# V2_0_2_USB_Hub_Switch.net
KiCad netlist of a schematic drawn in EasyEDA Pro
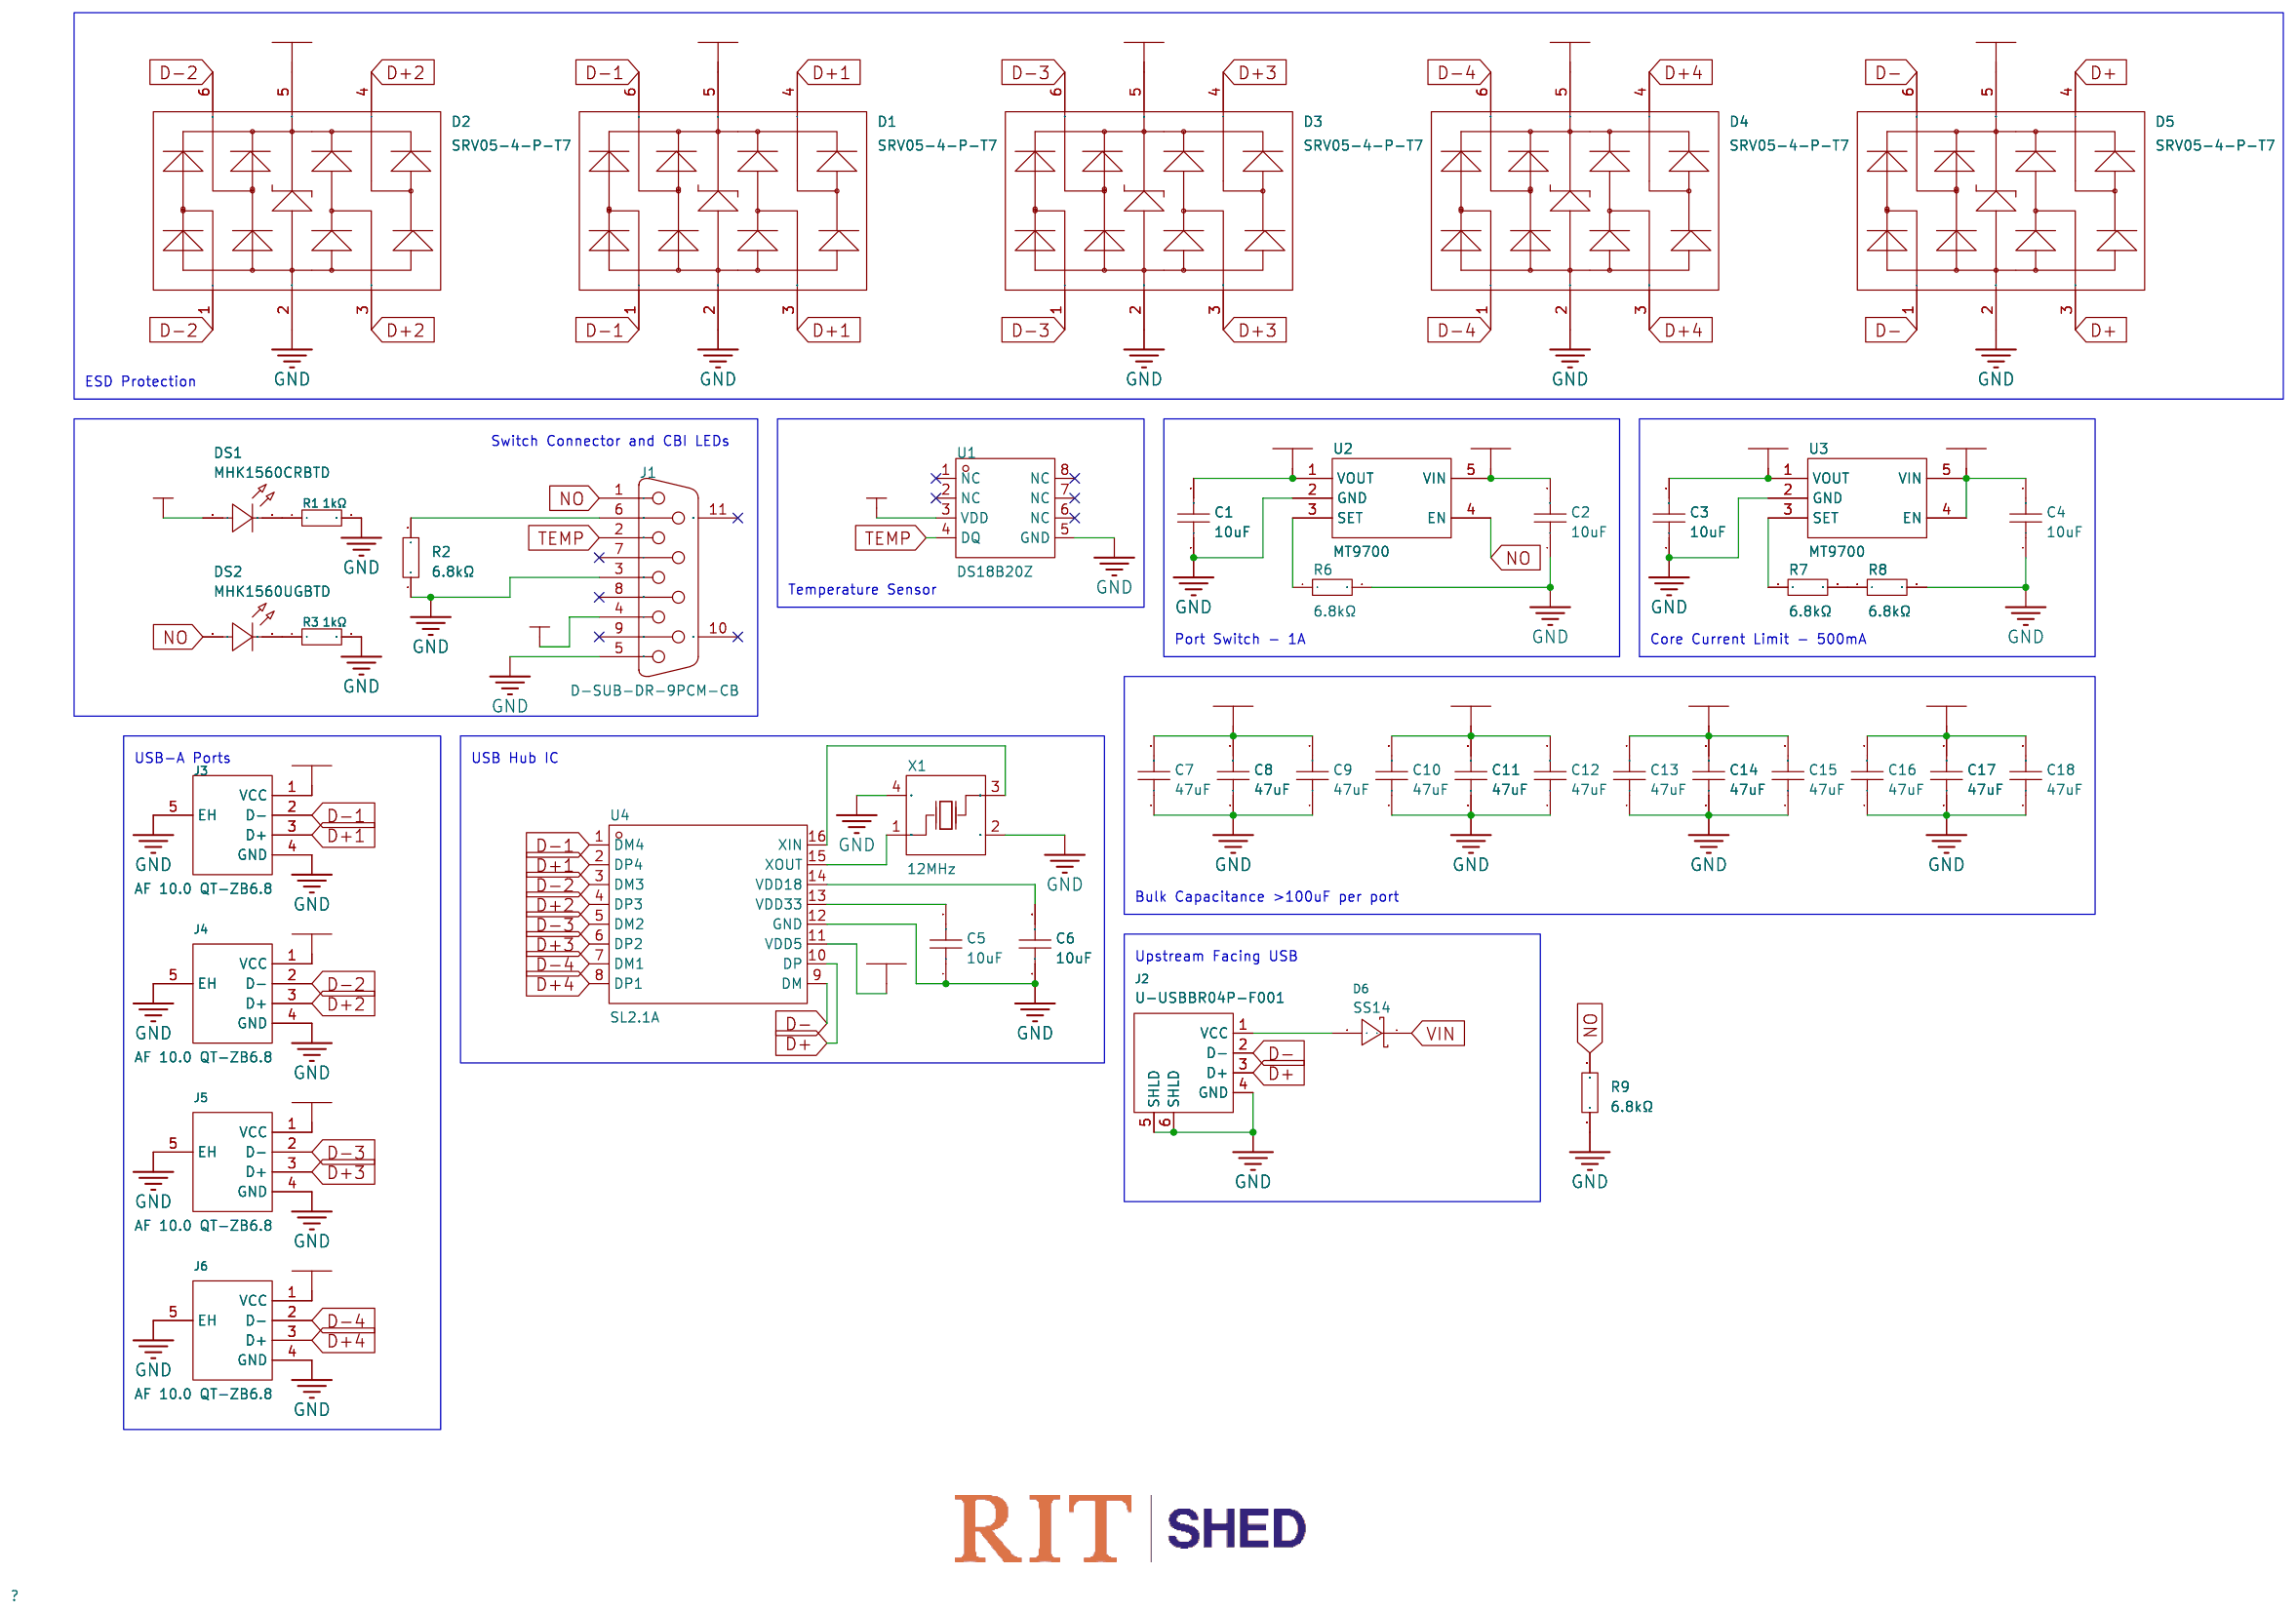
[diagram p0: schematic sheet]

(export (version "E")
  (design (tool "Eeschema 10.0.6"))
  (components
    (comp (ref "C1")
      (value "10uF")
      (footprint "easyedapro:C0603")
      (fields
        (field (name "Manufacturer Part") "CL10A106MA8NRNC")
        (field (name "Manufacturer") "SAMSUNG(三星)")
      )
      (libsource (lib "easyedapro") (part "CL10A106MA8NRNC"))
    )
    (comp (ref "C2")
      (value "10uF")
      (footprint "easyedapro:C0603")
      (fields
        (field (name "Manufacturer Part") "CL10A106MA8NRNC")
        (field (name "Manufacturer") "SAMSUNG(三星)")
      )
      (libsource (lib "easyedapro") (part "CL10A106MA8NRNC"))
    )
    (comp (ref "C3")
      (value "10uF")
      (footprint "easyedapro:C0603")
      (fields
        (field (name "Manufacturer Part") "CL10A106MA8NRNC")
        (field (name "Manufacturer") "SAMSUNG(三星)")
      )
      (libsource (lib "easyedapro") (part "CL10A106MA8NRNC"))
    )
    (comp (ref "C4")
      (value "10uF")
      (footprint "easyedapro:C0603")
      (fields
        (field (name "Manufacturer Part") "CL10A106MA8NRNC")
        (field (name "Manufacturer") "SAMSUNG(三星)")
      )
      (libsource (lib "easyedapro") (part "CL10A106MA8NRNC"))
    )
    (comp (ref "C5")
      (value "10uF")
      (footprint "easyedapro:C0603")
      (fields
        (field (name "Manufacturer Part") "CL10A106MA8NRNC")
        (field (name "Manufacturer") "SAMSUNG(三星)")
      )
      (libsource (lib "easyedapro") (part "CL10A106MA8NRNC"))
    )
    (comp (ref "C6")
      (value "10uF")
      (footprint "easyedapro:C0603")
      (fields
        (field (name "Manufacturer Part") "CL10A106MA8NRNC")
        (field (name "Manufacturer") "SAMSUNG(三星)")
      )
      (libsource (lib "easyedapro") (part "CL10A106MA8NRNC"))
    )
    (comp (ref "C7")
      (value "47uF")
      (footprint "easyedapro:C1206")
      (fields
        (field (name "Manufacturer Part") "CL31A476MPHNNNE")
        (field (name "Manufacturer") "SAMSUNG(三星)")
      )
      (libsource (lib "easyedapro") (part "CL31A476MPHNNNE"))
    )
    (comp (ref "C8")
      (value "47uF")
      (footprint "easyedapro:C1206")
      (fields
        (field (name "Manufacturer Part") "CL31A476MPHNNNE")
        (field (name "Manufacturer") "SAMSUNG(三星)")
      )
      (libsource (lib "easyedapro") (part "CL31A476MPHNNNE"))
    )
    (comp (ref "C9")
      (value "47uF")
      (footprint "easyedapro:C1206")
      (fields
        (field (name "Manufacturer Part") "CL31A476MPHNNNE")
        (field (name "Manufacturer") "SAMSUNG(三星)")
      )
      (libsource (lib "easyedapro") (part "CL31A476MPHNNNE"))
    )
    (comp (ref "C10")
      (value "47uF")
      (footprint "easyedapro:C1206")
      (fields
        (field (name "Manufacturer Part") "CL31A476MPHNNNE")
        (field (name "Manufacturer") "SAMSUNG(三星)")
      )
      (libsource (lib "easyedapro") (part "CL31A476MPHNNNE"))
    )
    (comp (ref "C11")
      (value "47uF")
      (footprint "easyedapro:C1206")
      (fields
        (field (name "Manufacturer Part") "CL31A476MPHNNNE")
        (field (name "Manufacturer") "SAMSUNG(三星)")
      )
      (libsource (lib "easyedapro") (part "CL31A476MPHNNNE"))
    )
    (comp (ref "C12")
      (value "47uF")
      (footprint "easyedapro:C1206")
      (fields
        (field (name "Manufacturer Part") "CL31A476MPHNNNE")
        (field (name "Manufacturer") "SAMSUNG(三星)")
      )
      (libsource (lib "easyedapro") (part "CL31A476MPHNNNE"))
    )
    (comp (ref "C13")
      (value "47uF")
      (footprint "easyedapro:C1206")
      (fields
        (field (name "Manufacturer Part") "CL31A476MPHNNNE")
        (field (name "Manufacturer") "SAMSUNG(三星)")
      )
      (libsource (lib "easyedapro") (part "CL31A476MPHNNNE"))
    )
    (comp (ref "C14")
      (value "47uF")
      (footprint "easyedapro:C1206")
      (fields
        (field (name "Manufacturer Part") "CL31A476MPHNNNE")
        (field (name "Manufacturer") "SAMSUNG(三星)")
      )
      (libsource (lib "easyedapro") (part "CL31A476MPHNNNE"))
    )
    (comp (ref "C15")
      (value "47uF")
      (footprint "easyedapro:C1206")
      (fields
        (field (name "Manufacturer Part") "CL31A476MPHNNNE")
        (field (name "Manufacturer") "SAMSUNG(三星)")
      )
      (libsource (lib "easyedapro") (part "CL31A476MPHNNNE"))
    )
    (comp (ref "C16")
      (value "47uF")
      (footprint "easyedapro:C1206")
      (fields
        (field (name "Manufacturer Part") "CL31A476MPHNNNE")
        (field (name "Manufacturer") "SAMSUNG(三星)")
      )
      (libsource (lib "easyedapro") (part "CL31A476MPHNNNE"))
    )
    (comp (ref "C17")
      (value "47uF")
      (footprint "easyedapro:C1206")
      (fields
        (field (name "Manufacturer Part") "CL31A476MPHNNNE")
        (field (name "Manufacturer") "SAMSUNG(三星)")
      )
      (libsource (lib "easyedapro") (part "CL31A476MPHNNNE"))
    )
    (comp (ref "C18")
      (value "47uF")
      (footprint "easyedapro:C1206")
      (fields
        (field (name "Manufacturer Part") "CL31A476MPHNNNE")
        (field (name "Manufacturer") "SAMSUNG(三星)")
      )
      (libsource (lib "easyedapro") (part "CL31A476MPHNNNE"))
    )
    (comp (ref "D1")
      (value "SRV05-4-P-T7")
      (footprint "easyedapro:SOT-23-6_L2.9-W1.6-P0.95-LS2.8-BR")
      (fields (field (name "Manufacturer") "PROTEK"))
      (libsource (lib "easyedapro") (part "SRV05-4-P-T7"))
    )
    (comp (ref "D2")
      (value "SRV05-4-P-T7")
      (footprint "easyedapro:SOT-23-6_L2.9-W1.6-P0.95-LS2.8-BR")
      (fields (field (name "Manufacturer") "PROTEK"))
      (libsource (lib "easyedapro") (part "SRV05-4-P-T7"))
    )
    (comp (ref "D3")
      (value "SRV05-4-P-T7")
      (footprint "easyedapro:SOT-23-6_L2.9-W1.6-P0.95-LS2.8-BR")
      (fields (field (name "Manufacturer") "PROTEK"))
      (libsource (lib "easyedapro") (part "SRV05-4-P-T7"))
    )
    (comp (ref "D4")
      (value "SRV05-4-P-T7")
      (footprint "easyedapro:SOT-23-6_L2.9-W1.6-P0.95-LS2.8-BR")
      (fields (field (name "Manufacturer") "PROTEK"))
      (libsource (lib "easyedapro") (part "SRV05-4-P-T7"))
    )
    (comp (ref "D5")
      (value "SRV05-4-P-T7")
      (footprint "easyedapro:SOT-23-6_L2.9-W1.6-P0.95-LS2.8-BR")
      (fields (field (name "Manufacturer") "PROTEK"))
      (libsource (lib "easyedapro") (part "SRV05-4-P-T7"))
    )
    (comp (ref "D6")
      (value "SS14")
      (footprint "easyedapro:SMA_L4.2-W2.6-LS5.3-RD")
      (fields (field (name "Manufacturer") "MDD"))
      (libsource (lib "easyedapro") (part "SS14"))
    )
    (comp (ref "DS1")
      (value "MHK1560CRBTD")
      (footprint "easyedapro:LED-TH_MHK1560UGBTD")
      (fields (field (name "Manufacturer") "MEIHUA(美华)"))
      (libsource (lib "easyedapro") (part "MHK1560CGBTD"))
    )
    (comp (ref "DS2")
      (value "MHK1560UGBTD")
      (footprint "easyedapro:LED-TH_MHK1560UGBTD")
      (fields (field (name "Manufacturer") "MEIHUA(美华)"))
      (libsource (lib "easyedapro") (part "MHK1560UGBTD"))
    )
    (comp (ref "J1")
      (value "D-SUB-DR-9PCM-CB")
      (footprint "easyedapro:DB9-TH_ID09S33E4GV00LF")
      (fields (field (name "Manufacturer") "XUNPU(讯普)"))
      (libsource (lib "easyedapro") (part "D-SUB-DR-9PCM-CB"))
    )
    (comp (ref "J2")
      (value "U-USBBR04P-F001")
      (footprint "easyedapro:USB-B-TH_U241-041N-1BR85-1")
      (fields (field (name "Manufacturer") "Ckmtw(灿科盟)"))
      (libsource (lib "easyedapro") (part "U-USBBR04P-F001"))
    )
    (comp (ref "J3")
      (value "AF 10.0 QT-ZB6.8")
      (footprint "easyedapro:USB-A-SMD_AF-10.0-QT-ZB6.8")
      (fields (field (name "Manufacturer") "SHOU HAN(首韩)"))
      (libsource (lib "easyedapro") (part "AF 10.0 QT-ZB6.8"))
    )
    (comp (ref "J4")
      (value "AF 10.0 QT-ZB6.8")
      (footprint "easyedapro:USB-A-SMD_AF-10.0-QT-ZB6.8")
      (fields (field (name "Manufacturer") "SHOU HAN(首韩)"))
      (libsource (lib "easyedapro") (part "AF 10.0 QT-ZB6.8"))
    )
    (comp (ref "J5")
      (value "AF 10.0 QT-ZB6.8")
      (footprint "easyedapro:USB-A-SMD_AF-10.0-QT-ZB6.8")
      (fields (field (name "Manufacturer") "SHOU HAN(首韩)"))
      (libsource (lib "easyedapro") (part "AF 10.0 QT-ZB6.8"))
    )
    (comp (ref "J6")
      (value "AF 10.0 QT-ZB6.8")
      (footprint "easyedapro:USB-A-SMD_AF-10.0-QT-ZB6.8")
      (fields (field (name "Manufacturer") "SHOU HAN(首韩)"))
      (libsource (lib "easyedapro") (part "AF 10.0 QT-ZB6.8"))
    )
    (comp (ref "R1")
      (value "1kΩ")
      (footprint "easyedapro:R0603")
      (fields
        (field (name "Manufacturer Part") "0603WAF1001T5E")
        (field (name "Manufacturer") "UNI-ROYAL(厚声)")
      )
      (libsource (lib "easyedapro") (part "0603WAF1001T5E"))
    )
    (comp (ref "R2")
      (value "6.8kΩ")
      (footprint "easyedapro:R0603")
      (fields
        (field (name "Manufacturer Part") "0603WAF6801T5E")
        (field (name "Manufacturer") "UNI-ROYAL(厚声)")
      )
      (libsource (lib "easyedapro") (part "0603WAF6801T5E"))
    )
    (comp (ref "R3")
      (value "1kΩ")
      (footprint "easyedapro:R0603")
      (fields
        (field (name "Manufacturer Part") "0603WAF1001T5E")
        (field (name "Manufacturer") "UNI-ROYAL(厚声)")
      )
      (libsource (lib "easyedapro") (part "0603WAF1001T5E"))
    )
    (comp (ref "R6")
      (value "6.8kΩ")
      (footprint "easyedapro:R0603")
      (fields
        (field (name "Manufacturer Part") "0603WAF6801T5E")
        (field (name "Manufacturer") "UNI-ROYAL(厚声)")
      )
      (libsource (lib "easyedapro") (part "0603WAF6801T5E"))
    )
    (comp (ref "R7")
      (value "6.8kΩ")
      (footprint "easyedapro:R0603")
      (fields
        (field (name "Manufacturer Part") "0603WAF6801T5E")
        (field (name "Manufacturer") "UNI-ROYAL(厚声)")
      )
      (libsource (lib "easyedapro") (part "0603WAF6801T5E"))
    )
    (comp (ref "R8")
      (value "6.8kΩ")
      (footprint "easyedapro:R0603")
      (fields
        (field (name "Manufacturer Part") "0603WAF6801T5E")
        (field (name "Manufacturer") "UNI-ROYAL(厚声)")
      )
      (libsource (lib "easyedapro") (part "0603WAF6801T5E"))
    )
    (comp (ref "R9")
      (value "6.8kΩ")
      (footprint "easyedapro:R0603")
      (fields
        (field (name "Manufacturer Part") "0603WAF6801T5E")
        (field (name "Manufacturer") "UNI-ROYAL(厚声)")
      )
      (libsource (lib "easyedapro") (part "0603WAF6801T5E"))
    )
    (comp (ref "U1")
      (value "DS18B20Z")
      (footprint "easyedapro:SOP-8_L4.9-W3.9-P1.27-LS6.0-BL")
      (description "Resolution:±0.4°C Resolution:±0.4°C Supply Voltage:2.5V~5.5V Supply Voltage:2.5V~5.5V")
      (fields (field (name "Manufacturer") "UMW(友台半导体)"))
      (libsource (lib "easyedapro") (part "DS18B20Z"))
    )
    (comp (ref "U2")
      (value "MT9700")
      (footprint "easyedapro:SOT-23-5_L3.0-W1.7-P0.95-LS2.8-BR")
      (fields (field (name "Manufacturer") "西安航天民芯"))
      (libsource (lib "easyedapro") (part "MT9700"))
    )
    (comp (ref "U3")
      (value "MT9700")
      (footprint "easyedapro:SOT-23-5_L3.0-W1.7-P0.95-LS2.8-BR")
      (fields (field (name "Manufacturer") "西安航天民芯"))
      (libsource (lib "easyedapro") (part "MT9700"))
    )
    (comp (ref "U4")
      (value "SL2.1A")
      (footprint "easyedapro:SOP-16_L10.0-W3.9-P1.27-LS6.0-BL")
      (fields (field (name "Manufacturer") "CoreChips(和芯润德)"))
      (libsource (lib "easyedapro") (part "SL2.1A"))
    )
    (comp (ref "X1")
      (value "12MHz")
      (footprint "easyedapro:OSC-SMD_4P-L3.2-W2.5-BL")
      (fields (field (name "Manufacturer Part") "X322512MSB4SI") (field (name "Manufacturer") "YXC(扬兴晶振)"))
      (libsource (lib "easyedapro") (part "X322512MSB4SI"))
    )
  )
  (nets
    (net (code "1") (name "D+") (class "Default")
      (node (ref "D5") (pin "3") (pinfunction "3_3") (pintype "input"))
      (node (ref "D5") (pin "4") (pinfunction "4_4") (pintype "input"))
      (node (ref "J2") (pin "3") (pinfunction "D+_3") (pintype "input"))
      (node (ref "U4") (pin "10") (pinfunction "DP_10") (pintype "input"))
    )
    (net (code "2") (name "D+1") (class "Default")
      (node (ref "D1") (pin "3") (pinfunction "3_3") (pintype "input"))
      (node (ref "D1") (pin "4") (pinfunction "4_4") (pintype "input"))
      (node (ref "J3") (pin "3") (pinfunction "D+_3") (pintype "input"))
      (node (ref "U4") (pin "2") (pinfunction "DP4_2") (pintype "input"))
    )
    (net (code "3") (name "D+2") (class "Default")
      (node (ref "D2") (pin "3") (pinfunction "3_3") (pintype "input"))
      (node (ref "D2") (pin "4") (pinfunction "4_4") (pintype "input"))
      (node (ref "J4") (pin "3") (pinfunction "D+_3") (pintype "input"))
      (node (ref "U4") (pin "4") (pinfunction "DP3_4") (pintype "input"))
    )
    (net (code "4") (name "D+3") (class "Default")
      (node (ref "D3") (pin "3") (pinfunction "3_3") (pintype "input"))
      (node (ref "D3") (pin "4") (pinfunction "4_4") (pintype "input"))
      (node (ref "J5") (pin "3") (pinfunction "D+_3") (pintype "input"))
      (node (ref "U4") (pin "6") (pinfunction "DP2_6") (pintype "input"))
    )
    (net (code "5") (name "D+4") (class "Default")
      (node (ref "D4") (pin "3") (pinfunction "3_3") (pintype "input"))
      (node (ref "D4") (pin "4") (pinfunction "4_4") (pintype "input"))
      (node (ref "J6") (pin "3") (pinfunction "D+_3") (pintype "input"))
      (node (ref "U4") (pin "8") (pinfunction "DP1_8") (pintype "input"))
    )
    (net (code "6") (name "D-") (class "Default")
      (node (ref "D5") (pin "1") (pinfunction "1_1") (pintype "input"))
      (node (ref "D5") (pin "6") (pinfunction "6_6") (pintype "input"))
      (node (ref "J2") (pin "2") (pinfunction "D-_2") (pintype "input"))
      (node (ref "U4") (pin "9") (pinfunction "DM_9") (pintype "input"))
    )
    (net (code "7") (name "D-1") (class "Default")
      (node (ref "D1") (pin "1") (pinfunction "1_1") (pintype "input"))
      (node (ref "D1") (pin "6") (pinfunction "6_6") (pintype "input"))
      (node (ref "J3") (pin "2") (pinfunction "D-_2") (pintype "input"))
      (node (ref "U4") (pin "1") (pinfunction "DM4_1") (pintype "input"))
    )
    (net (code "8") (name "D-2") (class "Default")
      (node (ref "D2") (pin "1") (pinfunction "1_1") (pintype "input"))
      (node (ref "D2") (pin "6") (pinfunction "6_6") (pintype "input"))
      (node (ref "J4") (pin "2") (pinfunction "D-_2") (pintype "input"))
      (node (ref "U4") (pin "3") (pinfunction "DM3_3") (pintype "input"))
    )
    (net (code "9") (name "D-3") (class "Default")
      (node (ref "D3") (pin "1") (pinfunction "1_1") (pintype "input"))
      (node (ref "D3") (pin "6") (pinfunction "6_6") (pintype "input"))
      (node (ref "J5") (pin "2") (pinfunction "D-_2") (pintype "input"))
      (node (ref "U4") (pin "5") (pinfunction "DM2_5") (pintype "input"))
    )
    (net (code "10") (name "D-4") (class "Default")
      (node (ref "D4") (pin "1") (pinfunction "1_1") (pintype "input"))
      (node (ref "D4") (pin "6") (pinfunction "6_6") (pintype "input"))
      (node (ref "J6") (pin "2") (pinfunction "D-_2") (pintype "input"))
      (node (ref "U4") (pin "7") (pinfunction "DM1_7") (pintype "input"))
    )
    (net (code "11") (name "GND") (class "Default")
      (node (ref "C1") (pin "1") (pinfunction "1_1") (pintype "input"))
      (node (ref "C10") (pin "1") (pinfunction "1_1") (pintype "input"))
      (node (ref "C11") (pin "1") (pinfunction "1_1") (pintype "input"))
      (node (ref "C12") (pin "1") (pinfunction "1_1") (pintype "input"))
      (node (ref "C13") (pin "1") (pinfunction "1_1") (pintype "input"))
      (node (ref "C14") (pin "1") (pinfunction "1_1") (pintype "input"))
      (node (ref "C15") (pin "1") (pinfunction "1_1") (pintype "input"))
      (node (ref "C16") (pin "1") (pinfunction "1_1") (pintype "input"))
      (node (ref "C17") (pin "1") (pinfunction "1_1") (pintype "input"))
      (node (ref "C18") (pin "1") (pinfunction "1_1") (pintype "input"))
      (node (ref "C2") (pin "1") (pinfunction "1_1") (pintype "input"))
      (node (ref "C3") (pin "1") (pinfunction "1_1") (pintype "input"))
      (node (ref "C4") (pin "1") (pinfunction "1_1") (pintype "input"))
      (node (ref "C5") (pin "1") (pinfunction "1_1") (pintype "input"))
      (node (ref "C6") (pin "1") (pinfunction "1_1") (pintype "input"))
      (node (ref "C7") (pin "1") (pinfunction "1_1") (pintype "input"))
      (node (ref "C8") (pin "1") (pinfunction "1_1") (pintype "input"))
      (node (ref "C9") (pin "1") (pinfunction "1_1") (pintype "input"))
      (node (ref "D1") (pin "2") (pinfunction "2_2") (pintype "input"))
      (node (ref "D2") (pin "2") (pinfunction "2_2") (pintype "input"))
      (node (ref "D3") (pin "2") (pinfunction "2_2") (pintype "input"))
      (node (ref "D4") (pin "2") (pinfunction "2_2") (pintype "input"))
      (node (ref "D5") (pin "2") (pinfunction "2_2") (pintype "input"))
      (node (ref "J1") (pin "3") (pinfunction "3_3") (pintype "input"))
      (node (ref "J1") (pin "5") (pinfunction "5_5") (pintype "input"))
      (node (ref "J2") (pin "4") (pinfunction "GND_4") (pintype "input"))
      (node (ref "J2") (pin "5") (pinfunction "SHLD_5") (pintype "input"))
      (node (ref "J2") (pin "6") (pinfunction "SHLD_6") (pintype "input"))
      (node (ref "J3") (pin "4") (pinfunction "GND_4") (pintype "input"))
      (node (ref "J3") (pin "5") (pinfunction "EH_5") (pintype "input"))
      (node (ref "J4") (pin "4") (pinfunction "GND_4") (pintype "input"))
      (node (ref "J4") (pin "5") (pinfunction "EH_5") (pintype "input"))
      (node (ref "J5") (pin "4") (pinfunction "GND_4") (pintype "input"))
      (node (ref "J5") (pin "5") (pinfunction "EH_5") (pintype "input"))
      (node (ref "J6") (pin "4") (pinfunction "GND_4") (pintype "input"))
      (node (ref "J6") (pin "5") (pinfunction "EH_5") (pintype "input"))
      (node (ref "R1") (pin "2") (pinfunction "2_2") (pintype "input"))
      (node (ref "R2") (pin "1") (pinfunction "1_1") (pintype "input"))
      (node (ref "R3") (pin "2") (pinfunction "2_2") (pintype "input"))
      (node (ref "R6") (pin "2") (pinfunction "2_2") (pintype "input"))
      (node (ref "R8") (pin "2") (pinfunction "2_2") (pintype "input"))
      (node (ref "R9") (pin "1") (pinfunction "1_1") (pintype "input"))
      (node (ref "U1") (pin "5") (pinfunction "GND_5") (pintype "unspecified"))
      (node (ref "U2") (pin "2") (pinfunction "GND_2") (pintype "input"))
      (node (ref "U3") (pin "2") (pinfunction "GND_2") (pintype "input"))
      (node (ref "U4") (pin "12") (pinfunction "GND_12") (pintype "input"))
      (node (ref "X1") (pin "2") (pinfunction "GND_2") (pintype "input"))
      (node (ref "X1") (pin "4") (pinfunction "GND_4") (pintype "input"))
    )
    (net (code "12") (name "NO") (class "Default")
      (node (ref "DS2") (pin "2") (pinfunction "A_2") (pintype "unspecified"))
      (node (ref "J1") (pin "1") (pinfunction "1_1") (pintype "input"))
      (node (ref "R9") (pin "2") (pinfunction "2_2") (pintype "input"))
      (node (ref "U2") (pin "4") (pinfunction "EN_4") (pintype "input"))
    )
    (net (code "13") (name "Net-(D6-A)") (class "Default")
      (node (ref "D6") (pin "2") (pinfunction "A_2") (pintype "unspecified"))
      (node (ref "J2") (pin "1") (pinfunction "VCC_1") (pintype "input"))
    )
    (net (code "14") (name "Net-(DS1-K)") (class "Default")
      (node (ref "DS1") (pin "1") (pinfunction "K_1") (pintype "unspecified"))
      (node (ref "R1") (pin "1") (pinfunction "1_1") (pintype "input"))
    )
    (net (code "15") (name "Net-(DS2-K)") (class "Default")
      (node (ref "DS2") (pin "1") (pinfunction "K_1") (pintype "unspecified"))
      (node (ref "R3") (pin "1") (pinfunction "1_1") (pintype "input"))
    )
    (net (code "16") (name "Net-(J1-Pad6)") (class "Default")
      (node (ref "J1") (pin "6") (pinfunction "6_6") (pintype "input"))
      (node (ref "R2") (pin "2") (pinfunction "2_2") (pintype "input"))
    )
    (net (code "17") (name "Net-(R7-Pad2)") (class "Default")
      (node (ref "R7") (pin "2") (pinfunction "2_2") (pintype "input"))
      (node (ref "R8") (pin "1") (pinfunction "1_1") (pintype "input"))
    )
    (net (code "18") (name "Net-(U2-SET)") (class "Default")
      (node (ref "R6") (pin "1") (pinfunction "1_1") (pintype "input"))
      (node (ref "U2") (pin "3") (pinfunction "SET_3") (pintype "input"))
    )
    (net (code "19") (name "Net-(U3-SET)") (class "Default")
      (node (ref "R7") (pin "1") (pinfunction "1_1") (pintype "input"))
      (node (ref "U3") (pin "3") (pinfunction "SET_3") (pintype "input"))
    )
    (net (code "20") (name "Net-(U4-VDD18)") (class "Default")
      (node (ref "C6") (pin "2") (pinfunction "2_2") (pintype "input"))
      (node (ref "U4") (pin "14") (pinfunction "VDD18_14") (pintype "input"))
    )
    (net (code "21") (name "Net-(U4-VDD33)") (class "Default")
      (node (ref "C5") (pin "2") (pinfunction "2_2") (pintype "input"))
      (node (ref "U4") (pin "13") (pinfunction "VDD33_13") (pintype "input"))
    )
    (net (code "22") (name "Net-(U4-XIN)") (class "Default")
      (node (ref "U4") (pin "16") (pinfunction "XIN_16") (pintype "input"))
      (node (ref "X1") (pin "3") (pinfunction "OSC2_3") (pintype "input"))
    )
    (net (code "23") (name "Net-(U4-XOUT)") (class "Default")
      (node (ref "U4") (pin "15") (pinfunction "XOUT_15") (pintype "input"))
      (node (ref "X1") (pin "1") (pinfunction "OSC1_1") (pintype "input"))
    )
    (net (code "24") (name "TEMP") (class "Default")
      (node (ref "J1") (pin "2") (pinfunction "2_2") (pintype "input"))
      (node (ref "U1") (pin "4") (pinfunction "DQ_4") (pintype "unspecified"))
    )
    (net (code "25") (name "VDS") (class "Default")
      (node (ref "C1") (pin "2") (pinfunction "2_2") (pintype "input"))
      (node (ref "C10") (pin "2") (pinfunction "2_2") (pintype "input"))
      (node (ref "C11") (pin "2") (pinfunction "2_2") (pintype "input"))
      (node (ref "C12") (pin "2") (pinfunction "2_2") (pintype "input"))
      (node (ref "C13") (pin "2") (pinfunction "2_2") (pintype "input"))
      (node (ref "C14") (pin "2") (pinfunction "2_2") (pintype "input"))
      (node (ref "C15") (pin "2") (pinfunction "2_2") (pintype "input"))
      (node (ref "C16") (pin "2") (pinfunction "2_2") (pintype "input"))
      (node (ref "C17") (pin "2") (pinfunction "2_2") (pintype "input"))
      (node (ref "C18") (pin "2") (pinfunction "2_2") (pintype "input"))
      (node (ref "C7") (pin "2") (pinfunction "2_2") (pintype "input"))
      (node (ref "C8") (pin "2") (pinfunction "2_2") (pintype "input"))
      (node (ref "C9") (pin "2") (pinfunction "2_2") (pintype "input"))
      (node (ref "D1") (pin "5") (pinfunction "5_5") (pintype "input"))
      (node (ref "D2") (pin "5") (pinfunction "5_5") (pintype "input"))
      (node (ref "D3") (pin "5") (pinfunction "5_5") (pintype "input"))
      (node (ref "D4") (pin "5") (pinfunction "5_5") (pintype "input"))
      (node (ref "J3") (pin "1") (pinfunction "VCC_1") (pintype "input"))
      (node (ref "J4") (pin "1") (pinfunction "VCC_1") (pintype "input"))
      (node (ref "J5") (pin "1") (pinfunction "VCC_1") (pintype "input"))
      (node (ref "J6") (pin "1") (pinfunction "VCC_1") (pintype "input"))
      (node (ref "U2") (pin "1") (pinfunction "VOUT_1") (pintype "input"))
    )
    (net (code "26") (name "VIN") (class "Default")
      (node (ref "C2") (pin "2") (pinfunction "2_2") (pintype "input"))
      (node (ref "C4") (pin "2") (pinfunction "2_2") (pintype "input"))
      (node (ref "D5") (pin "5") (pinfunction "5_5") (pintype "input"))
      (node (ref "D6") (pin "1") (pinfunction "K_1") (pintype "unspecified"))
      (node (ref "U2") (pin "5") (pinfunction "VIN_5") (pintype "input"))
      (node (ref "U3") (pin "4") (pinfunction "EN_4") (pintype "input"))
      (node (ref "U3") (pin "5") (pinfunction "VIN_5") (pintype "input"))
      (node (ref "U4") (pin "11") (pinfunction "VDD5_11") (pintype "input"))
    )
    (net (code "27") (name "VSW") (class "Default")
      (node (ref "C3") (pin "2") (pinfunction "2_2") (pintype "input"))
      (node (ref "DS1") (pin "2") (pinfunction "A_2") (pintype "unspecified"))
      (node (ref "J1") (pin "4") (pinfunction "4_4") (pintype "input"))
      (node (ref "U1") (pin "3") (pinfunction "VDD_3") (pintype "unspecified"))
      (node (ref "U3") (pin "1") (pinfunction "VOUT_1") (pintype "input"))
    )
    (net (code "28") (name "unconnected-(J1-MH1-Pad10)") (class "Default")
      (node (ref "J1") (pin "10") (pinfunction "MH1_10") (pintype "input+no_connect"))
    )
    (net (code "29") (name "unconnected-(J1-MH2-Pad11)") (class "Default")
      (node (ref "J1") (pin "11") (pinfunction "MH2_11") (pintype "input+no_connect"))
    )
    (net (code "30") (name "unconnected-(J1-Pad7)") (class "Default")
      (node (ref "J1") (pin "7") (pinfunction "7_7") (pintype "input+no_connect"))
    )
    (net (code "31") (name "unconnected-(J1-Pad8)") (class "Default")
      (node (ref "J1") (pin "8") (pinfunction "8_8") (pintype "input+no_connect"))
    )
    (net (code "32") (name "unconnected-(J1-Pad9)") (class "Default")
      (node (ref "J1") (pin "9") (pinfunction "9_9") (pintype "input+no_connect"))
    )
    (net (code "33") (name "unconnected-(U1-NC-Pad1)") (class "Default")
      (node (ref "U1") (pin "1") (pinfunction "NC_1") (pintype "unspecified+no_connect"))
    )
    (net (code "34") (name "unconnected-(U1-NC-Pad2)") (class "Default")
      (node (ref "U1") (pin "2") (pinfunction "NC_2") (pintype "unspecified+no_connect"))
    )
    (net (code "35") (name "unconnected-(U1-NC-Pad6)") (class "Default")
      (node (ref "U1") (pin "6") (pinfunction "NC_6") (pintype "unspecified+no_connect"))
    )
    (net (code "36") (name "unconnected-(U1-NC-Pad7)") (class "Default")
      (node (ref "U1") (pin "7") (pinfunction "NC_7") (pintype "unspecified+no_connect"))
    )
    (net (code "37") (name "unconnected-(U1-NC-Pad8)") (class "Default")
      (node (ref "U1") (pin "8") (pinfunction "NC_8") (pintype "unspecified+no_connect"))
    )
  )
)
